# 22_Nvidia_CAN.net
KiCad netlist of a schematic drawn in Altium Designer
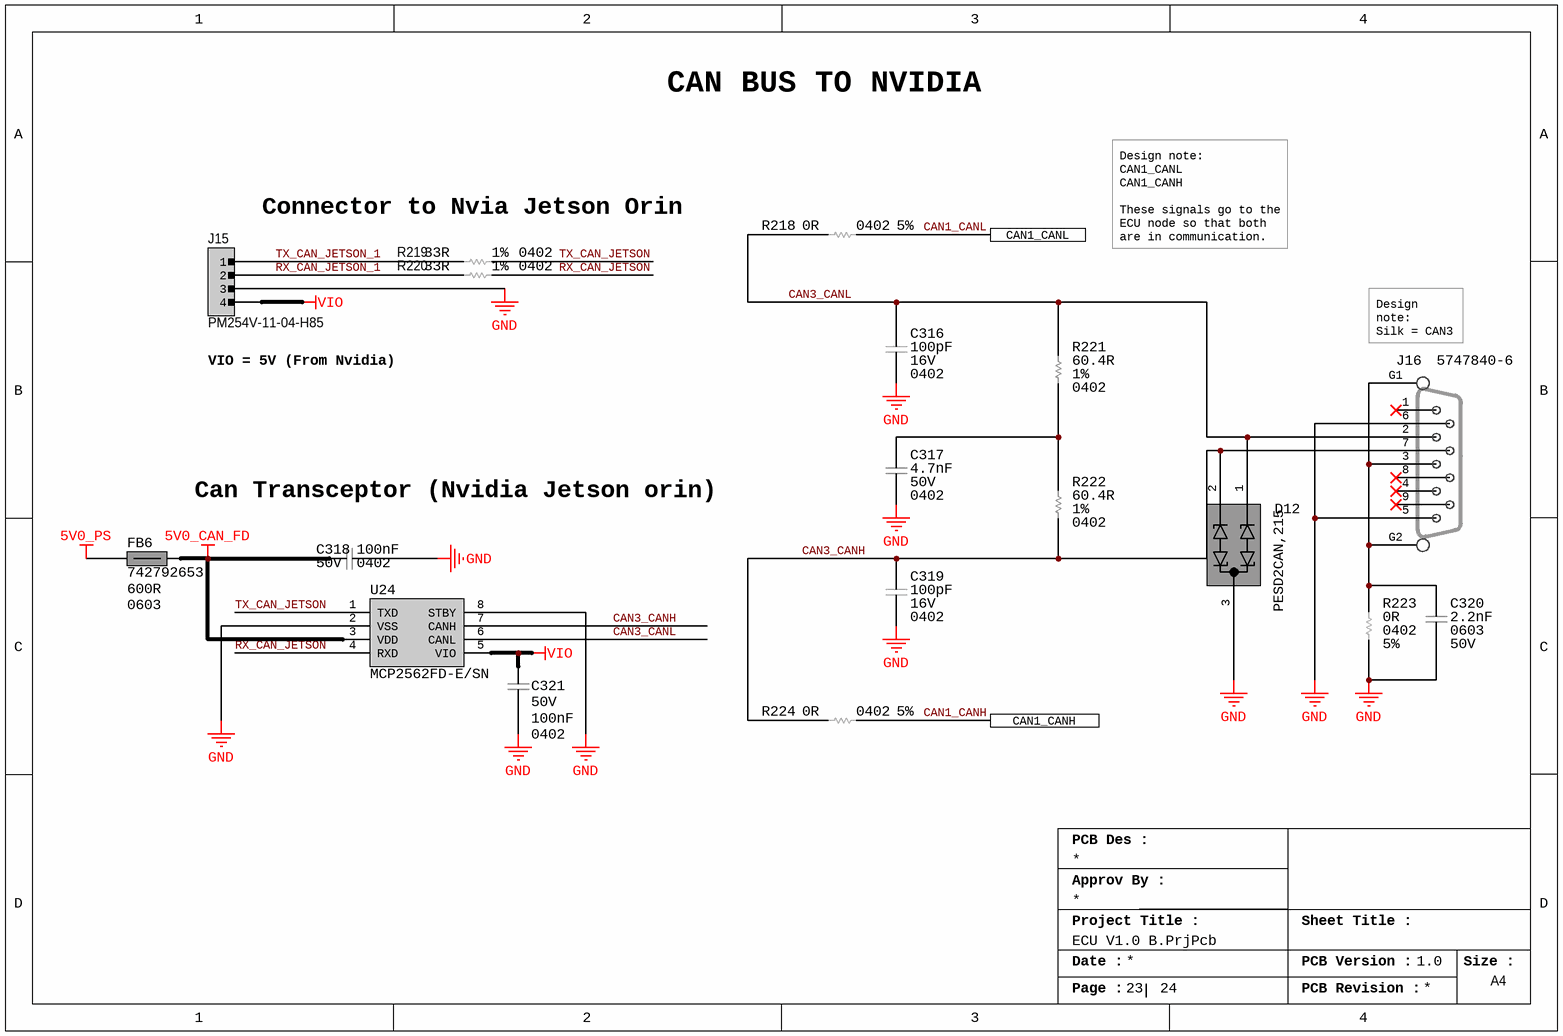
[diagram p0: 22_Nvidia_CAN.SchDoc]

(export (version "E")
  (design (tool "Eeschema 10.0.6"))
  (components
    (comp (ref "C316")
      (value "CC0402JRNPO7BN101")
      (footprint "CAP_0402_CAPC1005X05N")
      (description "0402 100 pF 16 V ±5 % Tolerance NP0 SMT Multilayer Ceramic Capacitor")
      (fields
        (field (name "MANUFACTURER") "Yageo")
        (field (name "TOLERANCE") "5%")
        (field (name "VOLTAGE RATING (DC)") "16V")
        (field (name "CAPACITANCE") "100pF")
        (field (name "CASE/PACKAGE") "0402")
      )
      (libsource (lib "Electronic Devices_LIB") (part "CAP_100PF_16V_NP0_0402"))
    )
    (comp (ref "C317")
      (value "GRM155R61H472KA01D")
      (footprint "CAP_0402_CAPC1005X05N")
      (description "Multilayer Ceramic Capacitor, 100 uF, 16 V, ± 20%, X5R, 1210 [3225 Metric]")
      (fields
        (field (name "MANUFACTURER") "Murata")
        (field (name "TOLERANCE") "10%")
        (field (name "VOLTAGE RATING") "50V")
        (field (name "CAPACITANCE") "4.7nF")
        (field (name "CASE/PACKAGE") "0402")
      )
      (libsource (lib "Electronic Devices_LIB") (part "CAP_4700PF_50V_X5R_0402"))
    )
    (comp (ref "C318")
      (value "GRM155R71H104KE14D")
      (footprint "CAP_0402_CAPC1005X05N")
      (description "Multilayer Ceramic Capacitor, 0.1 uF, 16 V, ± 10%, X7R, 0402 [1005 Metric]")
      (fields
        (field (name "MANUFACTURER") "Murata")
        (field (name "TOLERANCE") "10%")
        (field (name "VOLTAGE RATING") "50V")
        (field (name "CAPACITANCE") "100nF")
        (field (name "CASE/PACKAGE") "0402")
      )
      (libsource (lib "Electronic Devices_LIB") (part "CAP_100NF_50V_X7R_0402"))
    )
    (comp (ref "C319")
      (value "CC0402JRNPO7BN101")
      (footprint "CAP_0402_CAPC1005X05N")
      (description "0402 100 pF 16 V ±5 % Tolerance NP0 SMT Multilayer Ceramic Capacitor")
      (fields
        (field (name "MANUFACTURER") "Yageo")
        (field (name "TOLERANCE") "5%")
        (field (name "VOLTAGE RATING (DC)") "16V")
        (field (name "CAPACITANCE") "100pF")
        (field (name "CASE/PACKAGE") "0402")
      )
      (libsource (lib "Electronic Devices_LIB") (part "CAP_100PF_16V_NP0_0402"))
    )
    (comp (ref "C320")
      (value "GRM1885C1H222JA01D")
      (footprint "CAP_0603_CAPC1608X08N")
      (description "Multilayer Ceramic Capacitor, 2200 pF, 50 V, ï¿½ 5%, C0G (NP0), 0603 [1608 Metric]")
      (fields
        (field (name "MANUFACTURER") "Murata")
        (field (name "TOLERANCE") "5%")
        (field (name "CASE/PACKAGE") "0603")
        (field (name "VOLTAGE RATING") "50V")
        (field (name "CAPACITANCE") "2.2nF")
      )
      (libsource (lib "Electronic Devices_LIB") (part "CAP_2.2nF_50V_NP0_0402"))
    )
    (comp (ref "C321")
      (value "GRM155R71H104KE14D")
      (footprint "CAP_0402_CAPC1005X05N")
      (description "Multilayer Ceramic Capacitor, 0.1 uF, 16 V, ± 10%, X7R, 0402 [1005 Metric]")
      (fields
        (field (name "MANUFACTURER") "Murata")
        (field (name "TOLERANCE") "10%")
        (field (name "VOLTAGE RATING") "50V")
        (field (name "CAPACITANCE") "100nF")
        (field (name "CASE/PACKAGE") "0402")
      )
      (libsource (lib "Electronic Devices_LIB") (part "CAP_100NF_50V_X7R_0402"))
    )
    (comp (ref "D12")
      (value "PESD2CAN,215")
      (footprint "DIO_PESD2CAN,215")
      (description "5A 230W 41V 26.2V Bidirectional 24V SOT-23 ESD and Surge Protection (TVS/ESD) ROHS")
      (fields (field (name "MANUFACTURER") "Nexperia"))
      (libsource (lib "Electronic Devices_LIB") (part "DIO_TVS_41V_5A_PESD2CAN,215"))
    )
    (comp (ref "FB6")
      (value "742792653")
      (footprint "IND_0603_INDC1608X08N")
      (description "WE-CBF Ferrite Bead 0603 600Ohm 300mA ¦ Wurth Elektronik 742792653")
      (fields
        (field (name "MANUFACTURER") "Wurth Electronics")
        (field (name "TOLERANCE") "25%")
        (field (name "IMPEDANCE") "600R")
        (field (name "CASE CODE (IMPERIAL)") "0603")
      )
      (libsource (lib "Electronic Devices_LIB") (part "IND_FERRITE_BEADS_600R_300mA_0603_742792653"))
    )
    (comp (ref "J15")
      (value "PM254V-11-04-H85")
      (footprint "CONN_HEADER_FEM_4P")
      (description "2.54mm Plugin 4P Brass Straight 1x4P Plugin,P=2.54mm  Female Headers ROHS")
      (fields (field (name "MANUFACTURER") "XFCN") (field (name "JLCPCB PART NUMBER") "C541851"))
      (libsource (lib "Electronic Devices_LIB") (part "CONN_HEADER_FEMALE_4P_2.54mm_JLCPCB"))
    )
    (comp (ref "J16")
      (value "5747840-6")
      (footprint "TE_5747840-6")
      (description "D Subminiature Connector, 9 Contact(s), Male, 0.108 inch Pitch, Solder Terminal, #4-40, Plug")
      (fields (field (name "MANUFACTURER") "TE Connectivity"))
      (libsource (lib "Electronic Devices_LIB") (part "CONN_DB9_TEConnectivity_5747840-6"))
    )
    (comp (ref "R218")
      (value "ERJ-2GE0R00X")
      (footprint "RES_0402_RESC1005X04N")
      (description "SMD Chip Resistor, Jumper, 0 ohm, 100 mW, 0402 [1005 Metric], Thick Film, General Purpose")
      (fields
        (field (name "MANUFACTURER") "Panasonic")
        (field (name "CASE CODE (IMPERIAL)") "0402")
        (field (name "TOLERANCE") "5%")
        (field (name "RESISTANCE") "0R")
      )
      (libsource (lib "Electronic Devices_LIB") (part "RES_0R_5%_100mW_0402"))
    )
    (comp (ref "R219")
      (value "RC0402FR-0733RL")
      (footprint "RES_0402_RESC1005X04N")
      (description "SMD Chip Resistor, 33 Ohm, ± 1%, 62.5 mW, 0402 [1005 Metric], Thick Film, General Purpose")
      (fields
        (field (name "MANUFACTURER") "Yageo")
        (field (name "TOLERANCE") "1%")
        (field (name "RESISTANCE") "33R")
        (field (name "CASE/PACKAGE") "0402")
      )
      (libsource (lib "Electronic Devices_LIB") (part "RES_33R_1%_62.5mW_0402"))
    )
    (comp (ref "R220")
      (value "RC0402FR-0733RL")
      (footprint "RES_0402_RESC1005X04N")
      (description "SMD Chip Resistor, 33 Ohm, ± 1%, 62.5 mW, 0402 [1005 Metric], Thick Film, General Purpose")
      (fields
        (field (name "MANUFACTURER") "Yageo")
        (field (name "TOLERANCE") "1%")
        (field (name "RESISTANCE") "33R")
        (field (name "CASE/PACKAGE") "0402")
      )
      (libsource (lib "Electronic Devices_LIB") (part "RES_33R_1%_62.5mW_0402"))
    )
    (comp (ref "R221")
      (value "RK73H1ETTP60R4F")
      (footprint "RES_0402_RESC1005X04N")
      (description "Res Thick Film 0402 60.4 Ohm 1% 0.1W(1/10W) ±100ppm/C Pad SMD Automotive T/R")
      (fields
        (field (name "MANUFACTURER") "KOA Speer")
        (field (name "TOLERANCE") "1%")
        (field (name "RESISTANCE") "60.4R")
        (field (name "CASE/PACKAGE") "0402")
      )
      (libsource (lib "Electronic Devices_LIB") (part "RES_60.4R_1%_100mW_0402"))
    )
    (comp (ref "R222")
      (value "RK73H1ETTP60R4F")
      (footprint "RES_0402_RESC1005X04N")
      (description "Res Thick Film 0402 60.4 Ohm 1% 0.1W(1/10W) ±100ppm/C Pad SMD Automotive T/R")
      (fields
        (field (name "MANUFACTURER") "KOA Speer")
        (field (name "TOLERANCE") "1%")
        (field (name "RESISTANCE") "60.4R")
        (field (name "CASE/PACKAGE") "0402")
      )
      (libsource (lib "Electronic Devices_LIB") (part "RES_60.4R_1%_100mW_0402"))
    )
    (comp (ref "R223")
      (value "ERJ-2GE0R00X")
      (footprint "RES_0402_RESC1005X04N")
      (description "SMD Chip Resistor, Jumper, 0 ohm, 100 mW, 0402 [1005 Metric], Thick Film, General Purpose")
      (fields
        (field (name "MANUFACTURER") "Panasonic")
        (field (name "CASE CODE (IMPERIAL)") "0402")
        (field (name "TOLERANCE") "5%")
        (field (name "RESISTANCE") "0R")
      )
      (libsource (lib "Electronic Devices_LIB") (part "RES_0R_5%_100mW_0402"))
    )
    (comp (ref "R224")
      (value "ERJ-2GE0R00X")
      (footprint "RES_0402_RESC1005X04N")
      (description "SMD Chip Resistor, Jumper, 0 ohm, 100 mW, 0402 [1005 Metric], Thick Film, General Purpose")
      (fields
        (field (name "MANUFACTURER") "Panasonic")
        (field (name "CASE CODE (IMPERIAL)") "0402")
        (field (name "TOLERANCE") "5%")
        (field (name "RESISTANCE") "0R")
      )
      (libsource (lib "Electronic Devices_LIB") (part "RES_0R_5%_100mW_0402"))
    )
    (comp (ref "U24")
      (value "MCP2562FD-E/SN")
      (footprint "SOIC127P600X175-8N")
      (description "MCP2562 Series 5 V Surface Mount High-Speed CAN Transceiver - SOIC-8")
      (fields (field (name "MANUFACTURER") "Microchip"))
      (libsource (lib "Electronic Devices_LIB") (part "IC_TRANSCEIVER_CAN_MCP2562FD-E/SN"))
    )
  )
  (nets
    (net (code "1") (name "/CAN1_CANH") (class "Default")
      (node (ref "R224") (pin "2") (pinfunction "2_2") (pintype "passive"))
    )
    (net (code "2") (name "/CAN1_CANL") (class "Default")
      (node (ref "R218") (pin "2") (pinfunction "2_2") (pintype "passive"))
    )
    (net (code "3") (name "/CAN3_CANH") (class "Default")
      (node (ref "C319") (pin "2") (pinfunction "2_2") (pintype "passive"))
      (node (ref "D12") (pin "2") (pinfunction "C2_2") (pintype "passive"))
      (node (ref "J16") (pin "7") (pinfunction "7_7") (pintype "passive"))
      (node (ref "R222") (pin "1") (pinfunction "1_1") (pintype "passive"))
      (node (ref "R224") (pin "1") (pinfunction "1_1") (pintype "passive"))
      (node (ref "U24") (pin "7") (pinfunction "CANH_7") (pintype "passive"))
    )
    (net (code "4") (name "/CAN3_CANL") (class "Default")
      (node (ref "C316") (pin "2") (pinfunction "2_2") (pintype "passive"))
      (node (ref "D12") (pin "1") (pinfunction "C1_1") (pintype "passive"))
      (node (ref "J16") (pin "2") (pinfunction "2_2") (pintype "passive"))
      (node (ref "R218") (pin "1") (pinfunction "1_1") (pintype "passive"))
      (node (ref "R221") (pin "2") (pinfunction "2_2") (pintype "passive"))
      (node (ref "U24") (pin "6") (pinfunction "CANL_6") (pintype "passive"))
    )
    (net (code "5") (name "/RX_CAN_JETSON") (class "Default")
      (node (ref "R220") (pin "2") (pinfunction "2_2") (pintype "passive"))
      (node (ref "U24") (pin "4") (pinfunction "RXD_4") (pintype "passive"))
    )
    (net (code "6") (name "/RX_CAN_JETSON_1") (class "Default")
      (node (ref "J15") (pin "2") (pinfunction "2_2") (pintype "passive"))
      (node (ref "R220") (pin "1") (pinfunction "1_1") (pintype "passive"))
    )
    (net (code "7") (name "/TX_CAN_JETSON") (class "Default")
      (node (ref "R219") (pin "2") (pinfunction "2_2") (pintype "passive"))
      (node (ref "U24") (pin "1") (pinfunction "TXD_1") (pintype "passive"))
    )
    (net (code "8") (name "/TX_CAN_JETSON_1") (class "Default")
      (node (ref "J15") (pin "1") (pinfunction "1_1") (pintype "passive"))
      (node (ref "R219") (pin "1") (pinfunction "1_1") (pintype "passive"))
    )
    (net (code "9") (name "5V0_CAN_FD") (class "Default")
      (node (ref "C318") (pin "1") (pinfunction "1_1") (pintype "passive"))
      (node (ref "FB6") (pin "2") (pinfunction "2_2") (pintype "passive"))
      (node (ref "U24") (pin "3") (pinfunction "VDD_3") (pintype "passive"))
    )
    (net (code "10") (name "5V0_PS") (class "Default")
      (node (ref "FB6") (pin "1") (pinfunction "1_1") (pintype "passive"))
    )
    (net (code "11") (name "GND") (class "Default")
      (node (ref "C316") (pin "1") (pinfunction "1_1") (pintype "passive"))
      (node (ref "C317") (pin "1") (pinfunction "1_1") (pintype "passive"))
      (node (ref "C318") (pin "2") (pinfunction "2_2") (pintype "passive"))
      (node (ref "C319") (pin "1") (pinfunction "1_1") (pintype "passive"))
      (node (ref "C320") (pin "1") (pinfunction "1_1") (pintype "passive"))
      (node (ref "C321") (pin "2") (pinfunction "2_2") (pintype "passive"))
      (node (ref "D12") (pin "3") (pinfunction "CC_3") (pintype "passive"))
      (node (ref "J15") (pin "3") (pinfunction "3_3") (pintype "passive"))
      (node (ref "J16") (pin "5") (pinfunction "5_5") (pintype "passive"))
      (node (ref "J16") (pin "6") (pinfunction "6_6") (pintype "passive"))
      (node (ref "R223") (pin "1") (pinfunction "1_1") (pintype "passive"))
      (node (ref "U24") (pin "2") (pinfunction "VSS_2") (pintype "passive"))
      (node (ref "U24") (pin "8") (pinfunction "STBY_8") (pintype "passive"))
    )
    (net (code "12") (name "Net-(C317-Pad2)") (class "Default")
      (node (ref "C317") (pin "2") (pinfunction "2_2") (pintype "passive"))
      (node (ref "R221") (pin "1") (pinfunction "1_1") (pintype "passive"))
      (node (ref "R222") (pin "2") (pinfunction "2_2") (pintype "passive"))
    )
    (net (code "13") (name "Net-(J16-G)") (class "Default")
      (node (ref "C320") (pin "2") (pinfunction "2_2") (pintype "passive"))
      (node (ref "J16") (pin "3") (pinfunction "3_3") (pintype "passive"))
      (node (ref "J16") (pin "G1") (pinfunction "G1_G1") (pintype "passive"))
      (node (ref "J16") (pin "G2") (pinfunction "G_G2") (pintype "passive"))
      (node (ref "R223") (pin "2") (pinfunction "2_2") (pintype "passive"))
    )
    (net (code "14") (name "VIO") (class "Default")
      (node (ref "C321") (pin "1") (pinfunction "1_1") (pintype "passive"))
      (node (ref "J15") (pin "4") (pinfunction "4_4") (pintype "passive"))
      (node (ref "U24") (pin "5") (pinfunction "VIO_5") (pintype "passive"))
    )
    (net (code "15") (name "unconnected-(J16-Pad1)") (class "Default")
      (node (ref "J16") (pin "1") (pinfunction "1_1") (pintype "passive+no_connect"))
    )
    (net (code "16") (name "unconnected-(J16-Pad4)") (class "Default")
      (node (ref "J16") (pin "4") (pinfunction "4_4") (pintype "passive+no_connect"))
    )
    (net (code "17") (name "unconnected-(J16-Pad8)") (class "Default")
      (node (ref "J16") (pin "8") (pinfunction "8_8") (pintype "passive+no_connect"))
    )
    (net (code "18") (name "unconnected-(J16-Pad9)") (class "Default")
      (node (ref "J16") (pin "9") (pinfunction "9_9") (pintype "passive+no_connect"))
    )
  )
)
